# Periferals.net
KiCad netlist of a schematic drawn in Altium Designer
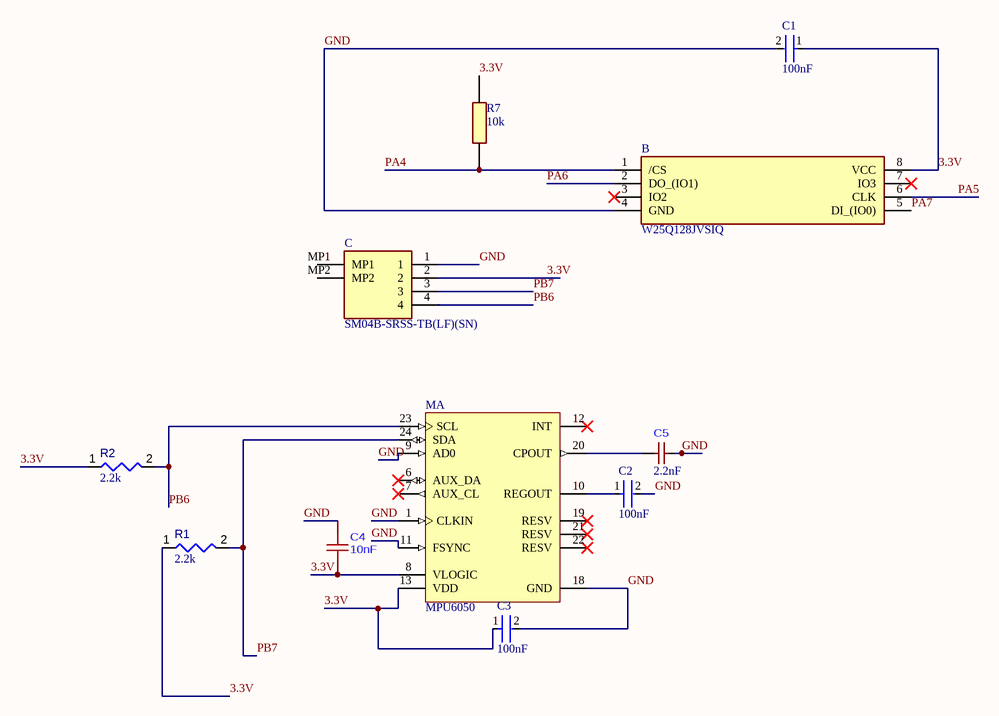
[diagram p0: Periferals.SchDoc]

(export (version "E")
  (design (tool "Eeschema 10.0.6"))
  (components
    (comp (ref "B")
      (value "W25Q128JVSIQ")
      (footprint "SOIC127P790X216-8N")
      (description "NOR Flash Serial (SPI, Dual SPI, Quad SPI) 3.3V 128M-bit 16M x 8 6ns 8-Pin SOIC Tube")
      (libsource (lib "Jegasoth") (part "W25Q128JVSIQ"))
    )
    (comp (ref "C")
      (value "SM04B-SRSS-TB(LF)(SN)")
      (footprint "SM04BSRSSTBLFSN")
      (description "Connector Header, Side Entry, SR Series, 4 Position, 1.00mm, 50V, Surface Mount, Tin, Natural")
      (libsource (lib "Jegasoth") (part "SM04B-SRSS-TB__LF__SN_"))
    )
    (comp (ref "C1")
      (value "100nF")
      (footprint "FP-CC0603-DA-IPC_B")
      (description "Multilayer Ceramic Capacitor, CC Series, 0.1 - F, - 10%, X7R, 50 V, 0603 [1608 Metric]")
      (fields (field (name "VOLTAGE") "50V") (field (name "TOLERANCE") "10%"))
      (libsource (lib "Jegasoth") (part "11868f565c42a9108669ba33697ecf6"))
    )
    (comp (ref "C2")
      (value "100nF")
      (footprint "FP-CC0603-DA-IPC_B")
      (description "Multilayer Ceramic Capacitor, CC Series, 0.1 - F, - 10%, X7R, 50 V, 0603 [1608 Metric]")
      (fields (field (name "VOLTAGE") "50V") (field (name "TOLERANCE") "10%"))
      (libsource (lib "Jegasoth") (part "11868f565c42a9108669ba33697ecf6"))
    )
    (comp (ref "C3")
      (value "100nF")
      (footprint "FP-CC0603-DA-IPC_B")
      (description "Multilayer Ceramic Capacitor, CC Series, 0.1 - F, - 10%, X7R, 50 V, 0603 [1608 Metric]")
      (fields (field (name "VOLTAGE") "50V") (field (name "TOLERANCE") "10%"))
      (libsource (lib "Jegasoth") (part "11868f565c42a9108669ba33697ecf6"))
    )
    (comp (ref "C4")
      (value "10nF")
      (footprint "PCBComponent_1")
      (description "50V 10nF X7R ±10% 0603 Multilayer Ceramic Capacitors MLCC - SMD/SMT ROHS")
      (fields (field (name "TOLERANCE") "10%"))
      (libsource (lib "Jegasoth") (part "0603B103K500NT"))
    )
    (comp (ref "C5")
      (value "2.2nF")
      (footprint "PCBComponent_1")
      (fields (field (name "Comment") "0603B222K500NT"))
      (libsource (lib "Jegasoth") (part "0603B222K500NT"))
    )
    (comp (ref "M")
      (value "MPU6050")
      (footprint "INSE-QFN-24_V")
      (fields (field (name "MANUFACTURER") "InvenSense"))
      (libsource (lib "Jegasoth") (part "INSE-MPU6050-QFN-24"))
    )
    (comp (ref "R1")
      (value "2.2k")
      (footprint "RESC0402(1005)_L")
      (description "Chip Resistor, 2,2 kOhms, +/-5 %, 63 mW, -55 to 155 degC, 0402")
      (fields (field (name "POWER") "63mW") (field (name "TOLERANCE") "5%"))
      (libsource (lib "Jegasoth") (part "RES-2"))
    )
    (comp (ref "R2")
      (value "2.2k")
      (footprint "RESC0402(1005)_L")
      (description "Chip Resistor, 2,2 kOhms, +/-5 %, 63 mW, -55 to 155 degC, 0402")
      (fields (field (name "POWER") "63mW") (field (name "TOLERANCE") "5%"))
      (libsource (lib "Jegasoth") (part "RES-2"))
    )
    (comp (ref "R7")
      (value "10k")
      (footprint "RESC1005X40N")
      (description "Res Thick Film 0402 10K Ohm 1% 0.063W(1/16W) ±100ppm/C Pad SMD T/R")
      (fields (field (name "TOLERANCE") "1%") (field (name "Comment") "0402WGF1002TCE"))
      (libsource (lib "Jegasoth") (part "0402WGF1002TCE"))
    )
  )
  (nets
    (net (code "1") (name "/3.3V") (class "Default")
      (node (ref "B") (pin "8") (pinfunction "VCC_8") (pintype "passive"))
      (node (ref "C") (pin "2") (pinfunction "2_2") (pintype "passive"))
      (node (ref "C1") (pin "1") (pinfunction "1_1") (pintype "passive"))
      (node (ref "C3") (pin "1") (pinfunction "1_1") (pintype "passive"))
      (node (ref "C4") (pin "1") (pinfunction "1_1") (pintype "passive"))
      (node (ref "M") (pin "13") (pinfunction "VDD_13") (pintype "power_in"))
      (node (ref "M") (pin "8") (pinfunction "VLOGIC_8") (pintype "power_in"))
      (node (ref "R1") (pin "1") (pinfunction "1_1") (pintype "passive"))
      (node (ref "R2") (pin "1") (pinfunction "1_1") (pintype "passive"))
      (node (ref "R7") (pin "2") (pinfunction "2_2") (pintype "passive"))
    )
    (net (code "2") (name "/GND") (class "Default")
      (node (ref "B") (pin "4") (pinfunction "GND_4") (pintype "passive"))
      (node (ref "C") (pin "1") (pinfunction "1_1") (pintype "passive"))
      (node (ref "C1") (pin "2") (pinfunction "2_2") (pintype "passive"))
      (node (ref "C2") (pin "2") (pinfunction "2_2") (pintype "passive"))
      (node (ref "C3") (pin "2") (pinfunction "2_2") (pintype "passive"))
      (node (ref "C4") (pin "2") (pinfunction "2_2") (pintype "passive"))
      (node (ref "C5") (pin "2") (pinfunction "2_2") (pintype "passive"))
      (node (ref "M") (pin "1") (pinfunction "CLKIN_1") (pintype "input"))
      (node (ref "M") (pin "11") (pinfunction "FSYNC_11") (pintype "input"))
      (node (ref "M") (pin "18") (pinfunction "GND_18") (pintype "power_in"))
      (node (ref "M") (pin "9") (pinfunction "AD0_9") (pintype "input"))
    )
    (net (code "3") (name "/PA4") (class "Default")
      (node (ref "B") (pin "1") (pinfunction "/CS_1") (pintype "passive"))
      (node (ref "R7") (pin "1") (pinfunction "1_1") (pintype "passive"))
    )
    (net (code "4") (name "/PA5") (class "Default")
      (node (ref "B") (pin "6") (pinfunction "CLK_6") (pintype "passive"))
    )
    (net (code "5") (name "/PA6") (class "Default")
      (node (ref "B") (pin "2") (pinfunction "DO_(IO1)_2") (pintype "passive"))
    )
    (net (code "6") (name "/PA7") (class "Default")
      (node (ref "B") (pin "5") (pinfunction "DI_(IO0)_5") (pintype "passive"))
    )
    (net (code "7") (name "/PB6") (class "Default")
      (node (ref "C") (pin "4") (pinfunction "4_4") (pintype "passive"))
      (node (ref "M") (pin "23") (pinfunction "SCL_23") (pintype "input"))
      (node (ref "R2") (pin "2") (pinfunction "2_2") (pintype "passive"))
    )
    (net (code "8") (name "/PB7") (class "Default")
      (node (ref "C") (pin "3") (pinfunction "3_3") (pintype "passive"))
      (node (ref "M") (pin "24") (pinfunction "SDA_24") (pintype "bidirectional"))
      (node (ref "R1") (pin "2") (pinfunction "2_2") (pintype "passive"))
    )
    (net (code "9") (name "Net-(MA-CPOUT)") (class "Default")
      (node (ref "C5") (pin "1") (pinfunction "1_1") (pintype "passive"))
      (node (ref "M") (pin "20") (pinfunction "CPOUT_20") (pintype "output"))
    )
    (net (code "10") (name "Net-(MA-REGOUT)") (class "Default")
      (node (ref "C2") (pin "1") (pinfunction "1_1") (pintype "passive"))
      (node (ref "M") (pin "10") (pinfunction "REGOUT_10") (pintype "passive"))
    )
    (net (code "11") (name "unconnected-(B-IO2-Pad3)") (class "Default")
      (node (ref "B") (pin "3") (pinfunction "IO2_3") (pintype "passive+no_connect"))
    )
    (net (code "12") (name "unconnected-(B-IO3-Pad7)") (class "Default")
      (node (ref "B") (pin "7") (pinfunction "IO3_7") (pintype "passive+no_connect"))
    )
    (net (code "13") (name "unconnected-(C-PadMP1)") (class "Default")
      (node (ref "C") (pin "MP1") (pinfunction "MP1_MP1") (pintype "passive"))
    )
    (net (code "14") (name "unconnected-(C-PadMP2)") (class "Default")
      (node (ref "C") (pin "MP2") (pinfunction "MP2_MP2") (pintype "passive"))
    )
    (net (code "15") (name "unconnected-(MA-AUX_CL-Pad7)") (class "Default")
      (node (ref "M") (pin "7") (pinfunction "AUX_CL_7") (pintype "output+no_connect"))
    )
    (net (code "16") (name "unconnected-(MA-AUX_DA-Pad6)") (class "Default")
      (node (ref "M") (pin "6") (pinfunction "AUX_DA_6") (pintype "bidirectional+no_connect"))
    )
    (net (code "17") (name "unconnected-(MA-INT-Pad12)") (class "Default")
      (node (ref "M") (pin "12") (pinfunction "INT_12") (pintype "open_collector+no_connect"))
    )
    (net (code "18") (name "unconnected-(MA-RESV-Pad19)") (class "Default")
      (node (ref "M") (pin "19") (pinfunction "RESV_19") (pintype "passive+no_connect"))
    )
    (net (code "19") (name "unconnected-(MA-RESV-Pad21)") (class "Default")
      (node (ref "M") (pin "21") (pinfunction "RESV_21") (pintype "passive+no_connect"))
    )
    (net (code "20") (name "unconnected-(MA-RESV-Pad22)") (class "Default")
      (node (ref "M") (pin "22") (pinfunction "RESV_22") (pintype "passive+no_connect"))
    )
  )
)
